# Input.net
KiCad netlist of a schematic drawn in Altium Designer
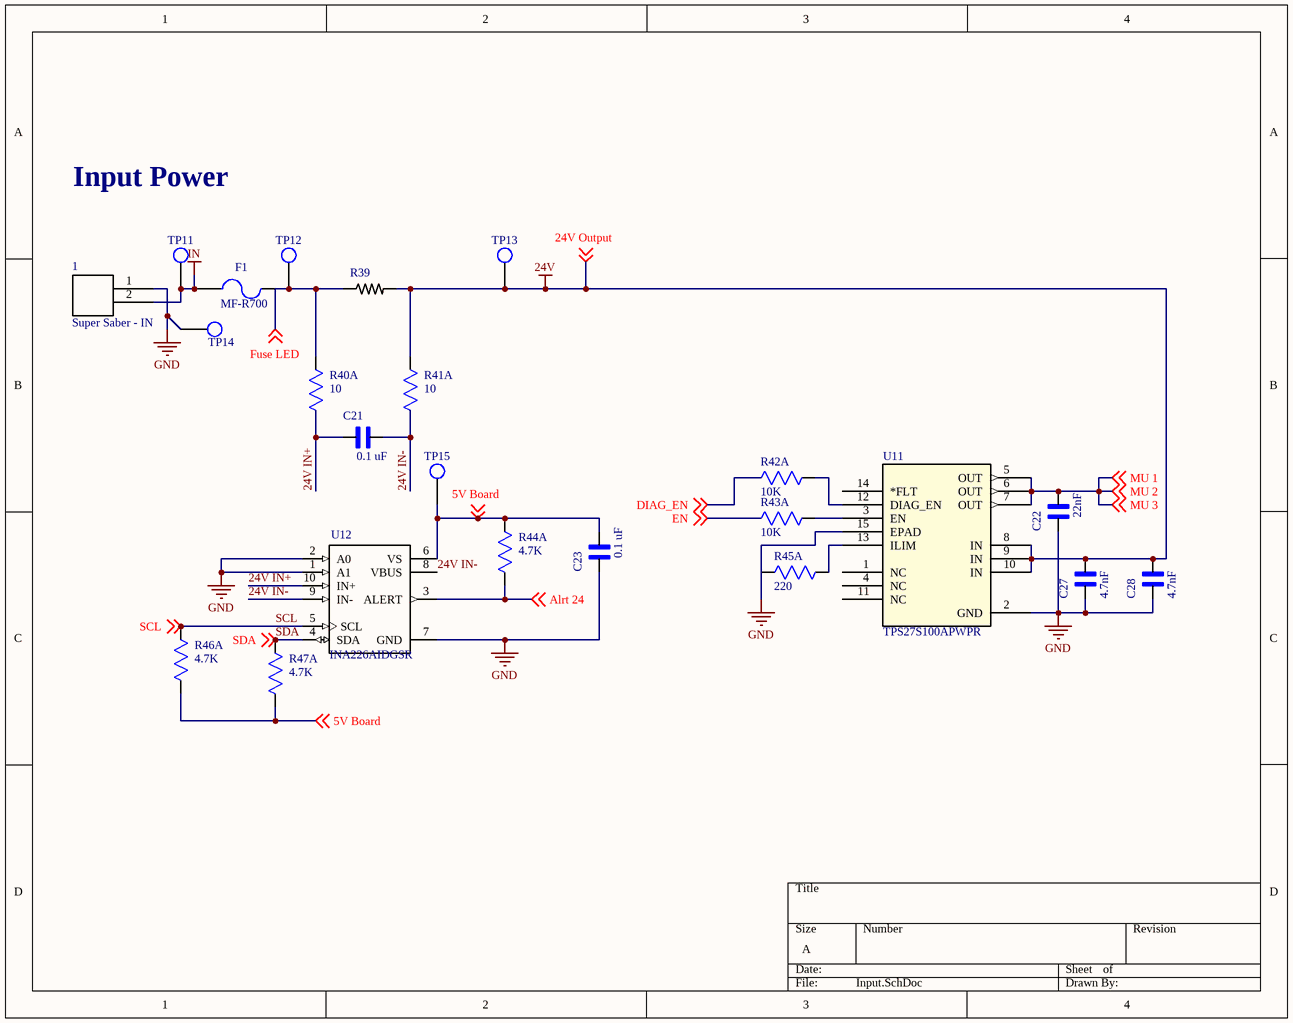
[diagram p0: Input.SchDoc]

(export (version "E")
  (design (tool "Eeschema 10.0.6"))
  (components
    (comp (ref "1")
      (value "Super Saber - IN")
      (footprint "0431600102")
      (libsource (lib "Connector Schematic Symbols") (part "Super Saber"))
    )
    (comp (ref "C21")
      (value "0.1 uF")
      (footprint "*CAPC2012X135N")
      (description "Cap Ceramic 2.2uF 16V X5R 10% SMD 0805 125Â°C Embossed T/R")
      (fields (field (name "MP") "EMK212BJ225KG-T") (field (name "DIGI-KEY_PART_NUMBER") "587-1293-1-ND"))
      (libsource (lib "EMK212BJ225KG-T") (part "EMK212BJ225KG-T"))
    )
    (comp (ref "C22")
      (value "22nF")
      (footprint "*CAPC2012X135N")
      (description "Cap Ceramic 2.2uF 16V X5R 10% SMD 0805 125Â°C Embossed T/R")
      (fields (field (name "MP") "EMK212BJ225KG-T") (field (name "DIGI-KEY_PART_NUMBER") "587-1293-1-ND"))
      (libsource (lib "EMK212BJ225KG-T") (part "EMK212BJ225KG-T"))
    )
    (comp (ref "C23")
      (value "0.1 uF")
      (footprint "*CAPC2012X135N")
      (description "Cap Ceramic 2.2uF 16V X5R 10% SMD 0805 125Â°C Embossed T/R")
      (fields (field (name "MP") "EMK212BJ225KG-T") (field (name "DIGI-KEY_PART_NUMBER") "587-1293-1-ND"))
      (libsource (lib "EMK212BJ225KG-T") (part "EMK212BJ225KG-T"))
    )
    (comp (ref "C27")
      (value "4.7nF")
      (footprint "*CAPC2012X135N")
      (description "Cap Ceramic 2.2uF 16V X5R 10% SMD 0805 125Â°C Embossed T/R")
      (fields (field (name "MP") "EMK212BJ225KG-T") (field (name "DIGI-KEY_PART_NUMBER") "587-1293-1-ND"))
      (libsource (lib "EMK212BJ225KG-T") (part "EMK212BJ225KG-T"))
    )
    (comp (ref "C28")
      (value "4.7nF")
      (footprint "*CAPC2012X135N")
      (description "Cap Ceramic 2.2uF 16V X5R 10% SMD 0805 125Â°C Embossed T/R")
      (fields (field (name "MP") "EMK212BJ225KG-T") (field (name "DIGI-KEY_PART_NUMBER") "587-1293-1-ND"))
      (libsource (lib "EMK212BJ225KG-T") (part "EMK212BJ225KG-T"))
    )
    (comp (ref "F1")
      (value "MF-R700")
      (footprint "New Fuse:*2920_FUSE")
      (description "Fuse")
      (fields (field (name "PUBLISHER") "Altium Limited"))
      (libsource (lib "Miscellaneous Devices") (part "Fuse 2"))
    )
    (comp (ref "R39")
      (value "1-1879378-2")
      (footprint "*RESC6331X70N")
      (description "TLR 2512 2.0W R003 1% 150PPM 2K RL")
      (fields (field (name "MP") "TLR3A20KR003FTDG") (field (name "MF") "TE Connectivity"))
      (libsource (lib "TLR3A20KR003FTDG") (part "TLR3A20KR003FTDG"))
    )
    (comp (ref "R40")
      (value "10")
      (footprint "RC0805N")
      (description "No Description Available")
      (fields
        (field (name "MANUFACTURER_PART_NUMBER") "CRCW0805681RFKEA_1")
        (field (name "COPYRIGHT") "Copyright (C) 2018 Accelerated Designs. All rights reserved")
      )
      (libsource (lib "2019-11-21_04-54-07") (part "CRCW0805681RFKEA"))
    )
    (comp (ref "R41")
      (value "10")
      (footprint "RC0805N")
      (description "No Description Available")
      (fields
        (field (name "MANUFACTURER_PART_NUMBER") "CRCW0805681RFKEA_1")
        (field (name "COPYRIGHT") "Copyright (C) 2018 Accelerated Designs. All rights reserved")
      )
      (libsource (lib "2019-11-21_04-54-07") (part "CRCW0805681RFKEA"))
    )
    (comp (ref "R42")
      (value "10K")
      (footprint "RC0805N")
      (description "No Description Available")
      (fields
        (field (name "MANUFACTURER_PART_NUMBER") "CRCW0805681RFKEA_1")
        (field (name "COPYRIGHT") "Copyright (C) 2018 Accelerated Designs. All rights reserved")
      )
      (libsource (lib "2019-11-21_04-54-07") (part "CRCW0805681RFKEA"))
    )
    (comp (ref "R43")
      (value "10K")
      (footprint "RC0805N")
      (description "No Description Available")
      (fields
        (field (name "MANUFACTURER_PART_NUMBER") "CRCW0805681RFKEA_1")
        (field (name "COPYRIGHT") "Copyright (C) 2018 Accelerated Designs. All rights reserved")
      )
      (libsource (lib "2019-11-21_04-54-07") (part "CRCW0805681RFKEA"))
    )
    (comp (ref "R44")
      (value "4.7K")
      (footprint "RC0805N")
      (description "No Description Available")
      (fields
        (field (name "MANUFACTURER_PART_NUMBER") "CRCW0805681RFKEA_1")
        (field (name "COPYRIGHT") "Copyright (C) 2018 Accelerated Designs. All rights reserved")
      )
      (libsource (lib "2019-11-21_04-54-07") (part "CRCW0805681RFKEA"))
    )
    (comp (ref "R45")
      (value "220")
      (footprint "RC0805N")
      (description "No Description Available")
      (fields
        (field (name "MANUFACTURER_PART_NUMBER") "CRCW0805681RFKEA_1")
        (field (name "COPYRIGHT") "Copyright (C) 2018 Accelerated Designs. All rights reserved")
      )
      (libsource (lib "2019-11-21_04-54-07") (part "CRCW0805681RFKEA"))
    )
    (comp (ref "R46")
      (value "4.7K")
      (footprint "RC0805N")
      (description "No Description Available")
      (fields
        (field (name "MANUFACTURER_PART_NUMBER") "CRCW0805681RFKEA_1")
        (field (name "COPYRIGHT") "Copyright (C) 2018 Accelerated Designs. All rights reserved")
      )
      (libsource (lib "2019-11-21_04-54-07") (part "CRCW0805681RFKEA"))
    )
    (comp (ref "R47")
      (value "4.7K")
      (footprint "RC0805N")
      (description "No Description Available")
      (fields
        (field (name "MANUFACTURER_PART_NUMBER") "CRCW0805681RFKEA_1")
        (field (name "COPYRIGHT") "Copyright (C) 2018 Accelerated Designs. All rights reserved")
      )
      (libsource (lib "2019-11-21_04-54-07") (part "CRCW0805681RFKEA"))
    )
    (comp (ref "TP11")
      (value "Test Point")
      (footprint "Test Point Through-hole")
      (libsource (lib "Test Points") (part "Test Point"))
    )
    (comp (ref "TP12")
      (value "Test Point")
      (footprint "Test Point Through-hole")
      (libsource (lib "Test Points") (part "Test Point"))
    )
    (comp (ref "TP13")
      (value "Test Point")
      (footprint "Test Point Through-hole")
      (libsource (lib "Test Points") (part "Test Point"))
    )
    (comp (ref "TP14")
      (value "Test Point")
      (footprint "Test Point Through-hole")
      (libsource (lib "Test Points") (part "Test Point"))
    )
    (comp (ref "TP15")
      (value "Test Point")
      (footprint "Test Point Through-hole")
      (libsource (lib "Test Points") (part "Test Point"))
    )
    (comp (ref "U11")
      (value "TPS27S100APWPR")
      (footprint "PWP14-M")
      (description "No Description Available")
      (fields (field (name "COPYRIGHT") "Copyright (C) 2018 Accelerated Designs. All rights reserved"))
      (libsource (lib "Power Switch 2") (part "TPS27S100APWPR"))
    )
    (comp (ref "U12")
      (value "INA226AIDGSR")
      (footprint "*SOP50P490X110-10N")
      (description "Current Monitor Regulator High/Low-Side 10mA 10-VSSOP")
      (fields (field (name "MF") "Texas Instruments") (field (name "DIGI-KEY_PART_NUMBER") "296-29034-1-ND"))
      (libsource (lib "INA226AIDGSR") (part "INA226AIDGSR"))
    )
  )
  (nets
    (net (code "1") (name "/24V IN+") (class "Default")
      (node (ref "C21") (pin "1") (pinfunction "1_1") (pintype "passive"))
      (node (ref "R40") (pin "2") (pinfunction "2_2") (pintype "passive"))
      (node (ref "U12") (pin "10") (pinfunction "IN+_10") (pintype "input"))
    )
    (net (code "2") (name "/24V IN-") (class "Default")
      (node (ref "C21") (pin "2") (pinfunction "2_2") (pintype "passive"))
      (node (ref "R41") (pin "2") (pinfunction "2_2") (pintype "passive"))
      (node (ref "U12") (pin "8") (pinfunction "VBUS_8") (pintype "power_in"))
      (node (ref "U12") (pin "9") (pinfunction "IN-_9") (pintype "input"))
    )
    (net (code "3") (name "5V Board") (class "Default")
      (node (ref "C23") (pin "2") (pinfunction "2_2") (pintype "passive"))
      (node (ref "R44") (pin "1") (pinfunction "1_1") (pintype "passive"))
      (node (ref "TP15") (pin "1") (pinfunction "1_1") (pintype "passive"))
      (node (ref "U12") (pin "6") (pinfunction "VS_6") (pintype "power_in"))
    )
    (net (code "4") (name "24V") (class "Default")
      (node (ref "C27") (pin "2") (pinfunction "2_2") (pintype "passive"))
      (node (ref "C28") (pin "2") (pinfunction "2_2") (pintype "passive"))
      (node (ref "R39") (pin "2") (pinfunction "2_2") (pintype "passive"))
      (node (ref "R41") (pin "1") (pinfunction "1_1") (pintype "passive"))
      (node (ref "TP13") (pin "1") (pinfunction "1_1") (pintype "passive"))
      (node (ref "U11") (pin "10") (pinfunction "IN_10") (pintype "passive"))
      (node (ref "U11") (pin "8") (pinfunction "IN_8") (pintype "passive"))
      (node (ref "U11") (pin "9") (pinfunction "IN_9") (pintype "passive"))
    )
    (net (code "5") (name "Alrt 24") (class "Default")
      (node (ref "U12") (pin "3") (pinfunction "ALERT_3") (pintype "output"))
    )
    (net (code "6") (name "DIAG_EN") (class "Default")
      (node (ref "R42") (pin "2") (pinfunction "2_2") (pintype "passive"))
    )
    (net (code "7") (name "EN") (class "Default")
      (node (ref "R43") (pin "2") (pinfunction "2_2") (pintype "passive"))
    )
    (net (code "8") (name "Fuse LED") (class "Default")
      (node (ref "F1") (pin "2") (pinfunction "2_2") (pintype "passive"))
      (node (ref "R39") (pin "1") (pinfunction "1_1") (pintype "passive"))
      (node (ref "R40") (pin "1") (pinfunction "1_1") (pintype "passive"))
      (node (ref "TP12") (pin "1") (pinfunction "1_1") (pintype "passive"))
    )
    (net (code "9") (name "GND") (class "Default")
      (node (ref "1") (pin "1") (pintype "passive"))
      (node (ref "C22") (pin "1") (pinfunction "1_1") (pintype "passive"))
      (node (ref "C23") (pin "1") (pinfunction "1_1") (pintype "passive"))
      (node (ref "C27") (pin "1") (pinfunction "1_1") (pintype "passive"))
      (node (ref "C28") (pin "1") (pinfunction "1_1") (pintype "passive"))
      (node (ref "TP14") (pin "1") (pinfunction "1_1") (pintype "passive"))
      (node (ref "U11") (pin "15") (pinfunction "EPAD_15") (pintype "passive"))
      (node (ref "U11") (pin "2") (pinfunction "GND_2") (pintype "passive"))
      (node (ref "U12") (pin "1") (pinfunction "A1_1") (pintype "input"))
      (node (ref "U12") (pin "2") (pinfunction "A0_2") (pintype "input"))
      (node (ref "U12") (pin "7") (pinfunction "GND_7") (pintype "power_in"))
    )
    (net (code "10") (name "IN") (class "Default")
      (node (ref "1") (pin "2") (pintype "passive"))
      (node (ref "F1") (pin "1") (pinfunction "1_1") (pintype "passive"))
      (node (ref "TP11") (pin "1") (pinfunction "1_1") (pintype "passive"))
    )
    (net (code "11") (name "MU 1") (class "Default")
      (node (ref "C22") (pin "2") (pinfunction "2_2") (pintype "passive"))
      (node (ref "U11") (pin "5") (pinfunction "OUT_5") (pintype "output"))
      (node (ref "U11") (pin "6") (pinfunction "OUT_6") (pintype "output"))
      (node (ref "U11") (pin "7") (pinfunction "OUT_7") (pintype "output"))
    )
    (net (code "12") (name "Net-(U11-DIAG_EN)") (class "Default")
      (node (ref "R42") (pin "1") (pinfunction "1_1") (pintype "passive"))
      (node (ref "U11") (pin "12") (pinfunction "DIAG_EN_12") (pintype "passive"))
    )
    (net (code "13") (name "Net-(U11-EN)") (class "Default")
      (node (ref "R43") (pin "1") (pinfunction "1_1") (pintype "passive"))
      (node (ref "U11") (pin "3") (pinfunction "EN_3") (pintype "passive"))
    )
    (net (code "14") (name "Net-(U11-ILIM)") (class "Default")
      (node (ref "R45") (pin "1") (pinfunction "1_1") (pintype "passive"))
      (node (ref "U11") (pin "13") (pinfunction "ILIM_13") (pintype "passive"))
    )
    (net (code "15") (name "SCL") (class "Default")
      (node (ref "R46") (pin "1") (pinfunction "1_1") (pintype "passive"))
      (node (ref "U12") (pin "5") (pinfunction "SCL_5") (pintype "input"))
    )
    (net (code "16") (name "SDA") (class "Default")
      (node (ref "R47") (pin "1") (pinfunction "1_1") (pintype "passive"))
      (node (ref "U12") (pin "4") (pinfunction "SDA_4") (pintype "bidirectional"))
    )
    (net (code "17") (name "unconnected-(R44-Pad2)") (class "Default")
      (node (ref "R44") (pin "2") (pinfunction "2_2") (pintype "passive"))
    )
    (net (code "18") (name "unconnected-(R45-Pad2)") (class "Default")
      (node (ref "R45") (pin "2") (pinfunction "2_2") (pintype "passive"))
    )
    (net (code "19") (name "unconnected-(R46-Pad2)") (class "Default")
      (node (ref "R46") (pin "2") (pinfunction "2_2") (pintype "passive"))
    )
    (net (code "20") (name "unconnected-(R47-Pad2)") (class "Default")
      (node (ref "R47") (pin "2") (pinfunction "2_2") (pintype "passive"))
    )
    (net (code "21") (name "unconnected-(U11-*FLT-Pad14)") (class "Default")
      (node (ref "U11") (pin "14") (pinfunction "*FLT_14") (pintype "passive"))
    )
    (net (code "22") (name "unconnected-(U11-NC-Pad1)") (class "Default")
      (node (ref "U11") (pin "1") (pinfunction "NC_1") (pintype "passive"))
    )
    (net (code "23") (name "unconnected-(U11-NC-Pad4)") (class "Default")
      (node (ref "U11") (pin "4") (pinfunction "NC_4") (pintype "passive"))
    )
    (net (code "24") (name "unconnected-(U11-NC-Pad11)") (class "Default")
      (node (ref "U11") (pin "11") (pinfunction "NC_11") (pintype "passive"))
    )
  )
)
